# Problem_2.net
KiCad netlist of a schematic drawn in Altium Designer
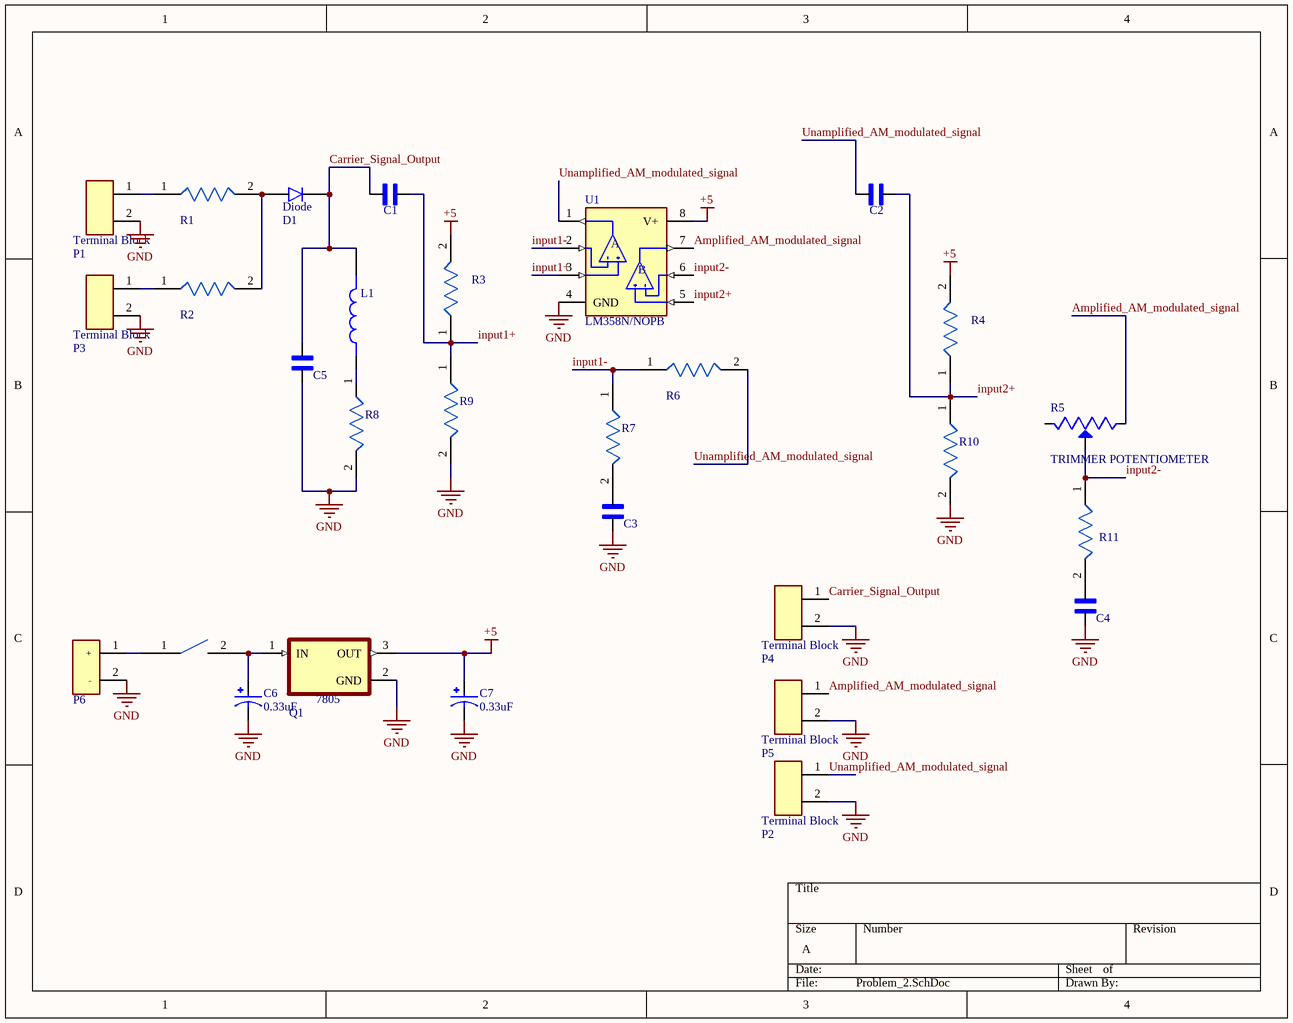
[diagram p0: Problem_2.SchDoc]

(export (version "E")
  (design (tool "Eeschema 10.0.6"))
  (components
    (comp (ref "*")
      (value "Switch")
      (footprint "Switch")
      (description "Rocker Switch")
      (libsource (lib "Problem_2_lib") (part "Switch"))
    )
    (comp (ref "C1")
      (value "Capacitor (10uF)")
      (footprint "Capacitor (10uF)")
      (description "10 ÂµF Â±10% 50V Ceramic Capacitor X7S Radial")
      (fields (field (name "MF") "TDK") (field (name "MP") "FG20X7S1H106KRT06"))
      (libsource (lib "") (part "Capacitor (10uF)_1"))
    )
    (comp (ref "C2")
      (value "Capacitor (10uF)")
      (footprint "Capacitor (10uF)")
      (description "10 ÂµF Â±10% 50V Ceramic Capacitor X7S Radial")
      (fields (field (name "MF") "TDK") (field (name "MP") "FG20X7S1H106KRT06"))
      (libsource (lib "") (part "Capacitor (10uF)_3"))
    )
    (comp (ref "C3")
      (value "Capacitor (10uF)")
      (footprint "Capacitor (10uF)")
      (description "10 ÂµF Â±10% 50V Ceramic Capacitor X7S Radial")
      (fields (field (name "MF") "TDK") (field (name "MP") "FG20X7S1H106KRT06"))
      (libsource (lib "Problem_2_lib") (part "Capacitor (10uF)"))
    )
    (comp (ref "C4")
      (value "Capacitor (10uF)")
      (footprint "Capacitor (10uF)")
      (description "10 ÂµF Â±10% 50V Ceramic Capacitor X7S Radial")
      (fields (field (name "MF") "TDK") (field (name "MP") "FG20X7S1H106KRT06"))
      (libsource (lib "") (part "Capacitor (10uF)_2"))
    )
    (comp (ref "C5")
      (value "Capacitor (10uF)")
      (footprint "Capacitor (10uF)")
      (description "10 ÂµF Â±10% 50V Ceramic Capacitor X7S Radial")
      (fields (field (name "MF") "TDK") (field (name "MP") "FG20X7S1H106KRT06"))
      (libsource (lib "Problem_2_lib") (part "Capacitor (10uF)"))
    )
    (comp (ref "C6")
      (value "0.33uF")
      (footprint "Capacitor (Polar)")
      (description "CAP ALUM 1UF 20% 50V RADIAL")
      (fields (field (name "MP") "EEU-EB1H1R0SB") (field (name "MF") "Panasonic Electronic Components"))
      (libsource (lib "Problem_2_lib") (part "Capacitor (Polar)"))
    )
    (comp (ref "C7")
      (value "0.33uF")
      (footprint "Capacitor (Polar)")
      (description "CAP ALUM 1UF 20% 50V RADIAL")
      (fields (field (name "MP") "EEU-EB1H1R0SB") (field (name "MF") "Panasonic Electronic Components"))
      (libsource (lib "Problem_2_lib") (part "Capacitor (Polar)"))
    )
    (comp (ref "D1")
      (value "Diode")
      (footprint "Diode")
      (description "1N-4148")
      (libsource (lib "Problem_2_lib") (part "Diode"))
    )
    (comp (ref "L1")
      (value "Inductor")
      (footprint "Inductor")
      (description "Inductor, 25.36Uh")
      (fields (field (name "MF") "Triad Magnetics") (field (name "MP") "FIT50-1"))
      (libsource (lib "Problem_2_lib") (part "Inductor"))
    )
    (comp (ref "P1")
      (value "Terminal Block 2 Pin")
      (footprint "Terminal Block 2 Pin")
      (description "2 pin")
      (fields (field (name "MF") "TE Connectivity") (field (name "MP") "282837-2"))
      (libsource (lib "Problem_2_lib") (part "Terminal Block 2 Pin"))
    )
    (comp (ref "P2")
      (value "Terminal Block 2 Pin")
      (footprint "Terminal Block 2 Pin")
      (description "2 pin")
      (fields (field (name "MF") "TE Connectivity") (field (name "MP") "282837-2"))
      (libsource (lib "Problem_2_lib") (part "Terminal Block 2 Pin"))
    )
    (comp (ref "P3")
      (value "Terminal Block 2 Pin")
      (footprint "Terminal Block 2 Pin")
      (description "2 pin")
      (fields (field (name "MF") "TE Connectivity") (field (name "MP") "282837-2"))
      (libsource (lib "Problem_2_lib") (part "Terminal Block 2 Pin"))
    )
    (comp (ref "P4")
      (value "~")
      (footprint "Terminal Block 2 Pin")
      (description "2 pin")
      (fields (field (name "MF") "TE Connectivity") (field (name "MP") "282837-2"))
      (libsource (lib "Problem_2_lib") (part "Terminal Block 2 Pin"))
    )
    (comp (ref "P5")
      (value "~")
      (footprint "Terminal Block 2 Pin")
      (description "2 pin")
      (fields (field (name "MF") "TE Connectivity") (field (name "MP") "282837-2"))
      (libsource (lib "Problem_2_lib") (part "Terminal Block 2 Pin"))
    )
    (comp (ref "P6")
      (value "HEADER, 2 PINS")
      (footprint "XT60 Male")
      (description "CONNECTOR")
      (libsource (lib "Problem_2_lib") (part "XT60 MALE"))
    )
    (comp (ref "Q1")
      (value "LM7805CT/NOPB")
      (footprint "LM7805CT/NOPB - duplicate")
      (description "1.5-A, 30-V, linear voltage regulator")
      (fields (field (name "MP") "LM7805CT") (field (name "MF") "Comset Semiconductors"))
      (libsource (lib "Fahim") (part "LM7805CT/NOPB"))
    )
    (comp (ref "R1")
      (value "Resistor (10k)")
      (footprint "Resistor (10k)")
      (libsource (lib "Problem_2_lib") (part "Resistor (10k)"))
    )
    (comp (ref "R2")
      (value "Resistor (10k)")
      (footprint "Resistor (10k)")
      (libsource (lib "Problem_2_lib") (part "Resistor (10k)"))
    )
    (comp (ref "R3")
      (value "Resistor (4.7k)")
      (footprint "Resistor (4.7k)")
      (libsource (lib "Problem_2_lib") (part "Resistor (4.7k)"))
    )
    (comp (ref "R4")
      (value "Resistor (4.7k)")
      (footprint "Resistor (4.7k)")
      (libsource (lib "Problem_2_lib") (part "Resistor (4.7k)"))
    )
    (comp (ref "R5")
      (value "TRIMMER POTENTIOMETER")
      (footprint "Potentiometer (trimmer)")
      (description "VARIABLE RESISTOR")
      (libsource (lib "Problem_2_lib") (part "TRIMMER POTENTIOMETER"))
    )
    (comp (ref "R6")
      (value "Resistor (4.7k)")
      (footprint "Resistor (4.7k)")
      (libsource (lib "Problem_2_lib") (part "Resistor (4.7k)"))
    )
    (comp (ref "R7")
      (value "Resistor (1k)")
      (footprint "Resistor (1k)")
      (libsource (lib "Problem_2_lib") (part "Resistor (1k)"))
    )
    (comp (ref "R8")
      (value "Resistor (0.5R)")
      (footprint "Resistor (0.5R)")
      (libsource (lib "Problem_2_lib") (part "Resistor (0.5R)"))
    )
    (comp (ref "R9")
      (value "Resistor (4.7k)")
      (footprint "Resistor (4.7k)")
      (libsource (lib "Problem_2_lib") (part "Resistor (4.7k)"))
    )
    (comp (ref "R10")
      (value "Resistor (4.7k)")
      (footprint "Resistor (4.7k)")
      (libsource (lib "Problem_2_lib") (part "Resistor (4.7k)"))
    )
    (comp (ref "R11")
      (value "Resistor (1k)")
      (footprint "Resistor (1k)")
      (libsource (lib "Problem_2_lib") (part "Resistor (1k)"))
    )
    (comp (ref "U1")
      (value "LM358N/NOPB")
      (footprint "LM358N")
      (description "General Purpose Amplifier 2 Circuit - 8-PDIP")
      (fields (field (name "MF") "ON Semiconductor") (field (name "MP") "LM358N"))
      (libsource (lib "Problem_2_lib") (part "LM358N/NOPB"))
    )
  )
  (nets
    (net (code "1") (name "+5") (class "Default")
      (node (ref "C7") (pin "P") (pinfunction "P_P") (pintype "passive"))
      (node (ref "Q1") (pin "3") (pinfunction "OUT_3") (pintype "output"))
      (node (ref "R3") (pin "2") (pintype "passive"))
      (node (ref "R4") (pin "2") (pintype "passive"))
      (node (ref "U1") (pin "8") (pinfunction "V+_8") (pintype "power_in"))
    )
    (net (code "2") (name "/Amplified_AM_modulated_signal") (class "Default")
      (node (ref "P5") (pin "1") (pinfunction "1_1") (pintype "passive"))
      (node (ref "R5") (pin "1") (pinfunction "CCW_1") (pintype "passive"))
      (node (ref "U1") (pin "7") (pinfunction "OUTB_7") (pintype "output"))
    )
    (net (code "3") (name "/Carrier_Signal_Output") (class "Default")
      (node (ref "C1") (pin "1") (pinfunction "1_1") (pintype "passive"))
      (node (ref "C5") (pin "1") (pinfunction "1_1") (pintype "passive"))
      (node (ref "D1") (pin "2") (pinfunction "Cathode_2") (pintype "passive"))
      (node (ref "L1") (pin "2") (pinfunction "2_2") (pintype "passive"))
      (node (ref "P4") (pin "1") (pinfunction "1_1") (pintype "passive"))
    )
    (net (code "4") (name "/Unamplified_AM_modulated_signal") (class "Default")
      (node (ref "C2") (pin "2") (pinfunction "2_2") (pintype "passive"))
      (node (ref "P2") (pin "1") (pinfunction "1_1") (pintype "passive"))
      (node (ref "R6") (pin "2") (pintype "passive"))
      (node (ref "U1") (pin "1") (pinfunction "OUTA_1") (pintype "output"))
    )
    (net (code "5") (name "/input1+") (class "Default")
      (node (ref "C1") (pin "2") (pinfunction "2_2") (pintype "passive"))
      (node (ref "R3") (pin "1") (pintype "passive"))
      (node (ref "R9") (pin "1") (pintype "passive"))
      (node (ref "U1") (pin "3") (pinfunction "+INA_3") (pintype "input"))
    )
    (net (code "6") (name "/input1-") (class "Default")
      (node (ref "R6") (pin "1") (pintype "passive"))
      (node (ref "R7") (pin "1") (pintype "passive"))
      (node (ref "U1") (pin "2") (pinfunction "-INA_2") (pintype "input"))
    )
    (net (code "7") (name "/input2+") (class "Default")
      (node (ref "C2") (pin "1") (pinfunction "1_1") (pintype "passive"))
      (node (ref "R10") (pin "1") (pintype "passive"))
      (node (ref "R4") (pin "1") (pintype "passive"))
      (node (ref "U1") (pin "5") (pinfunction "+INB_5") (pintype "input"))
    )
    (net (code "8") (name "/input2-") (class "Default")
      (node (ref "R11") (pin "1") (pintype "passive"))
      (node (ref "R5") (pin "2") (pinfunction "WIPER_2") (pintype "passive"))
      (node (ref "U1") (pin "6") (pinfunction "-INB_6") (pintype "input"))
    )
    (net (code "9") (name "GND") (class "Default")
      (node (ref "C3") (pin "2") (pinfunction "2_2") (pintype "passive"))
      (node (ref "C4") (pin "1") (pinfunction "1_1") (pintype "passive"))
      (node (ref "C5") (pin "2") (pinfunction "2_2") (pintype "passive"))
      (node (ref "C6") (pin "N") (pinfunction "N_N") (pintype "passive"))
      (node (ref "C7") (pin "N") (pinfunction "N_N") (pintype "passive"))
      (node (ref "P1") (pin "2") (pinfunction "2_2") (pintype "passive"))
      (node (ref "P2") (pin "2") (pinfunction "2_2") (pintype "passive"))
      (node (ref "P3") (pin "2") (pinfunction "2_2") (pintype "passive"))
      (node (ref "P4") (pin "2") (pinfunction "2_2") (pintype "passive"))
      (node (ref "P5") (pin "2") (pinfunction "2_2") (pintype "passive"))
      (node (ref "P6") (pin "2") (pinfunction "-_2") (pintype "passive"))
      (node (ref "Q1") (pin "2") (pinfunction "GND_2") (pintype "power_in"))
      (node (ref "R10") (pin "2") (pintype "passive"))
      (node (ref "R8") (pin "2") (pintype "passive"))
      (node (ref "R9") (pin "2") (pintype "passive"))
      (node (ref "U1") (pin "4") (pinfunction "GND_4") (pintype "power_in"))
    )
    (net (code "10") (name "Net-(*-8)") (class "Default")
      (node (ref "*") (pin "1") (pinfunction "8_1") (pintype "passive"))
      (node (ref "P6") (pin "1") (pinfunction "+_1") (pintype "passive"))
    )
    (net (code "11") (name "Net-(*-9)") (class "Default")
      (node (ref "*") (pin "2") (pinfunction "9_2") (pintype "passive"))
      (node (ref "C6") (pin "P") (pinfunction "P_P") (pintype "passive"))
      (node (ref "Q1") (pin "1") (pinfunction "IN_1") (pintype "input"))
    )
    (net (code "12") (name "Net-(C3-Pad1)") (class "Default")
      (node (ref "C3") (pin "1") (pinfunction "1_1") (pintype "passive"))
      (node (ref "R7") (pin "2") (pintype "passive"))
    )
    (net (code "13") (name "Net-(C4-Pad2)") (class "Default")
      (node (ref "C4") (pin "2") (pinfunction "2_2") (pintype "passive"))
      (node (ref "R11") (pin "2") (pintype "passive"))
    )
    (net (code "14") (name "Net-(D1-Anode)") (class "Default")
      (node (ref "D1") (pin "1") (pinfunction "Anode_1") (pintype "passive"))
      (node (ref "R1") (pin "2") (pintype "passive"))
      (node (ref "R2") (pin "2") (pintype "passive"))
    )
    (net (code "15") (name "Net-(L1-Pad1)") (class "Default")
      (node (ref "L1") (pin "1") (pinfunction "1_1") (pintype "passive"))
      (node (ref "R8") (pin "1") (pintype "passive"))
    )
    (net (code "16") (name "Net-(P1-Pad1)") (class "Default")
      (node (ref "P1") (pin "1") (pinfunction "1_1") (pintype "passive"))
      (node (ref "R1") (pin "1") (pintype "passive"))
    )
    (net (code "17") (name "Net-(P3-Pad1)") (class "Default")
      (node (ref "P3") (pin "1") (pinfunction "1_1") (pintype "passive"))
      (node (ref "R2") (pin "1") (pintype "passive"))
    )
    (net (code "18") (name "unconnected-(R5-CW-Pad3)") (class "Default")
      (node (ref "R5") (pin "3") (pinfunction "CW_3") (pintype "passive"))
    )
  )
)
